# SCH_Voltage-Regulator-AMS1117_2026-08-26.net
KiCad netlist of a schematic drawn in EasyEDA
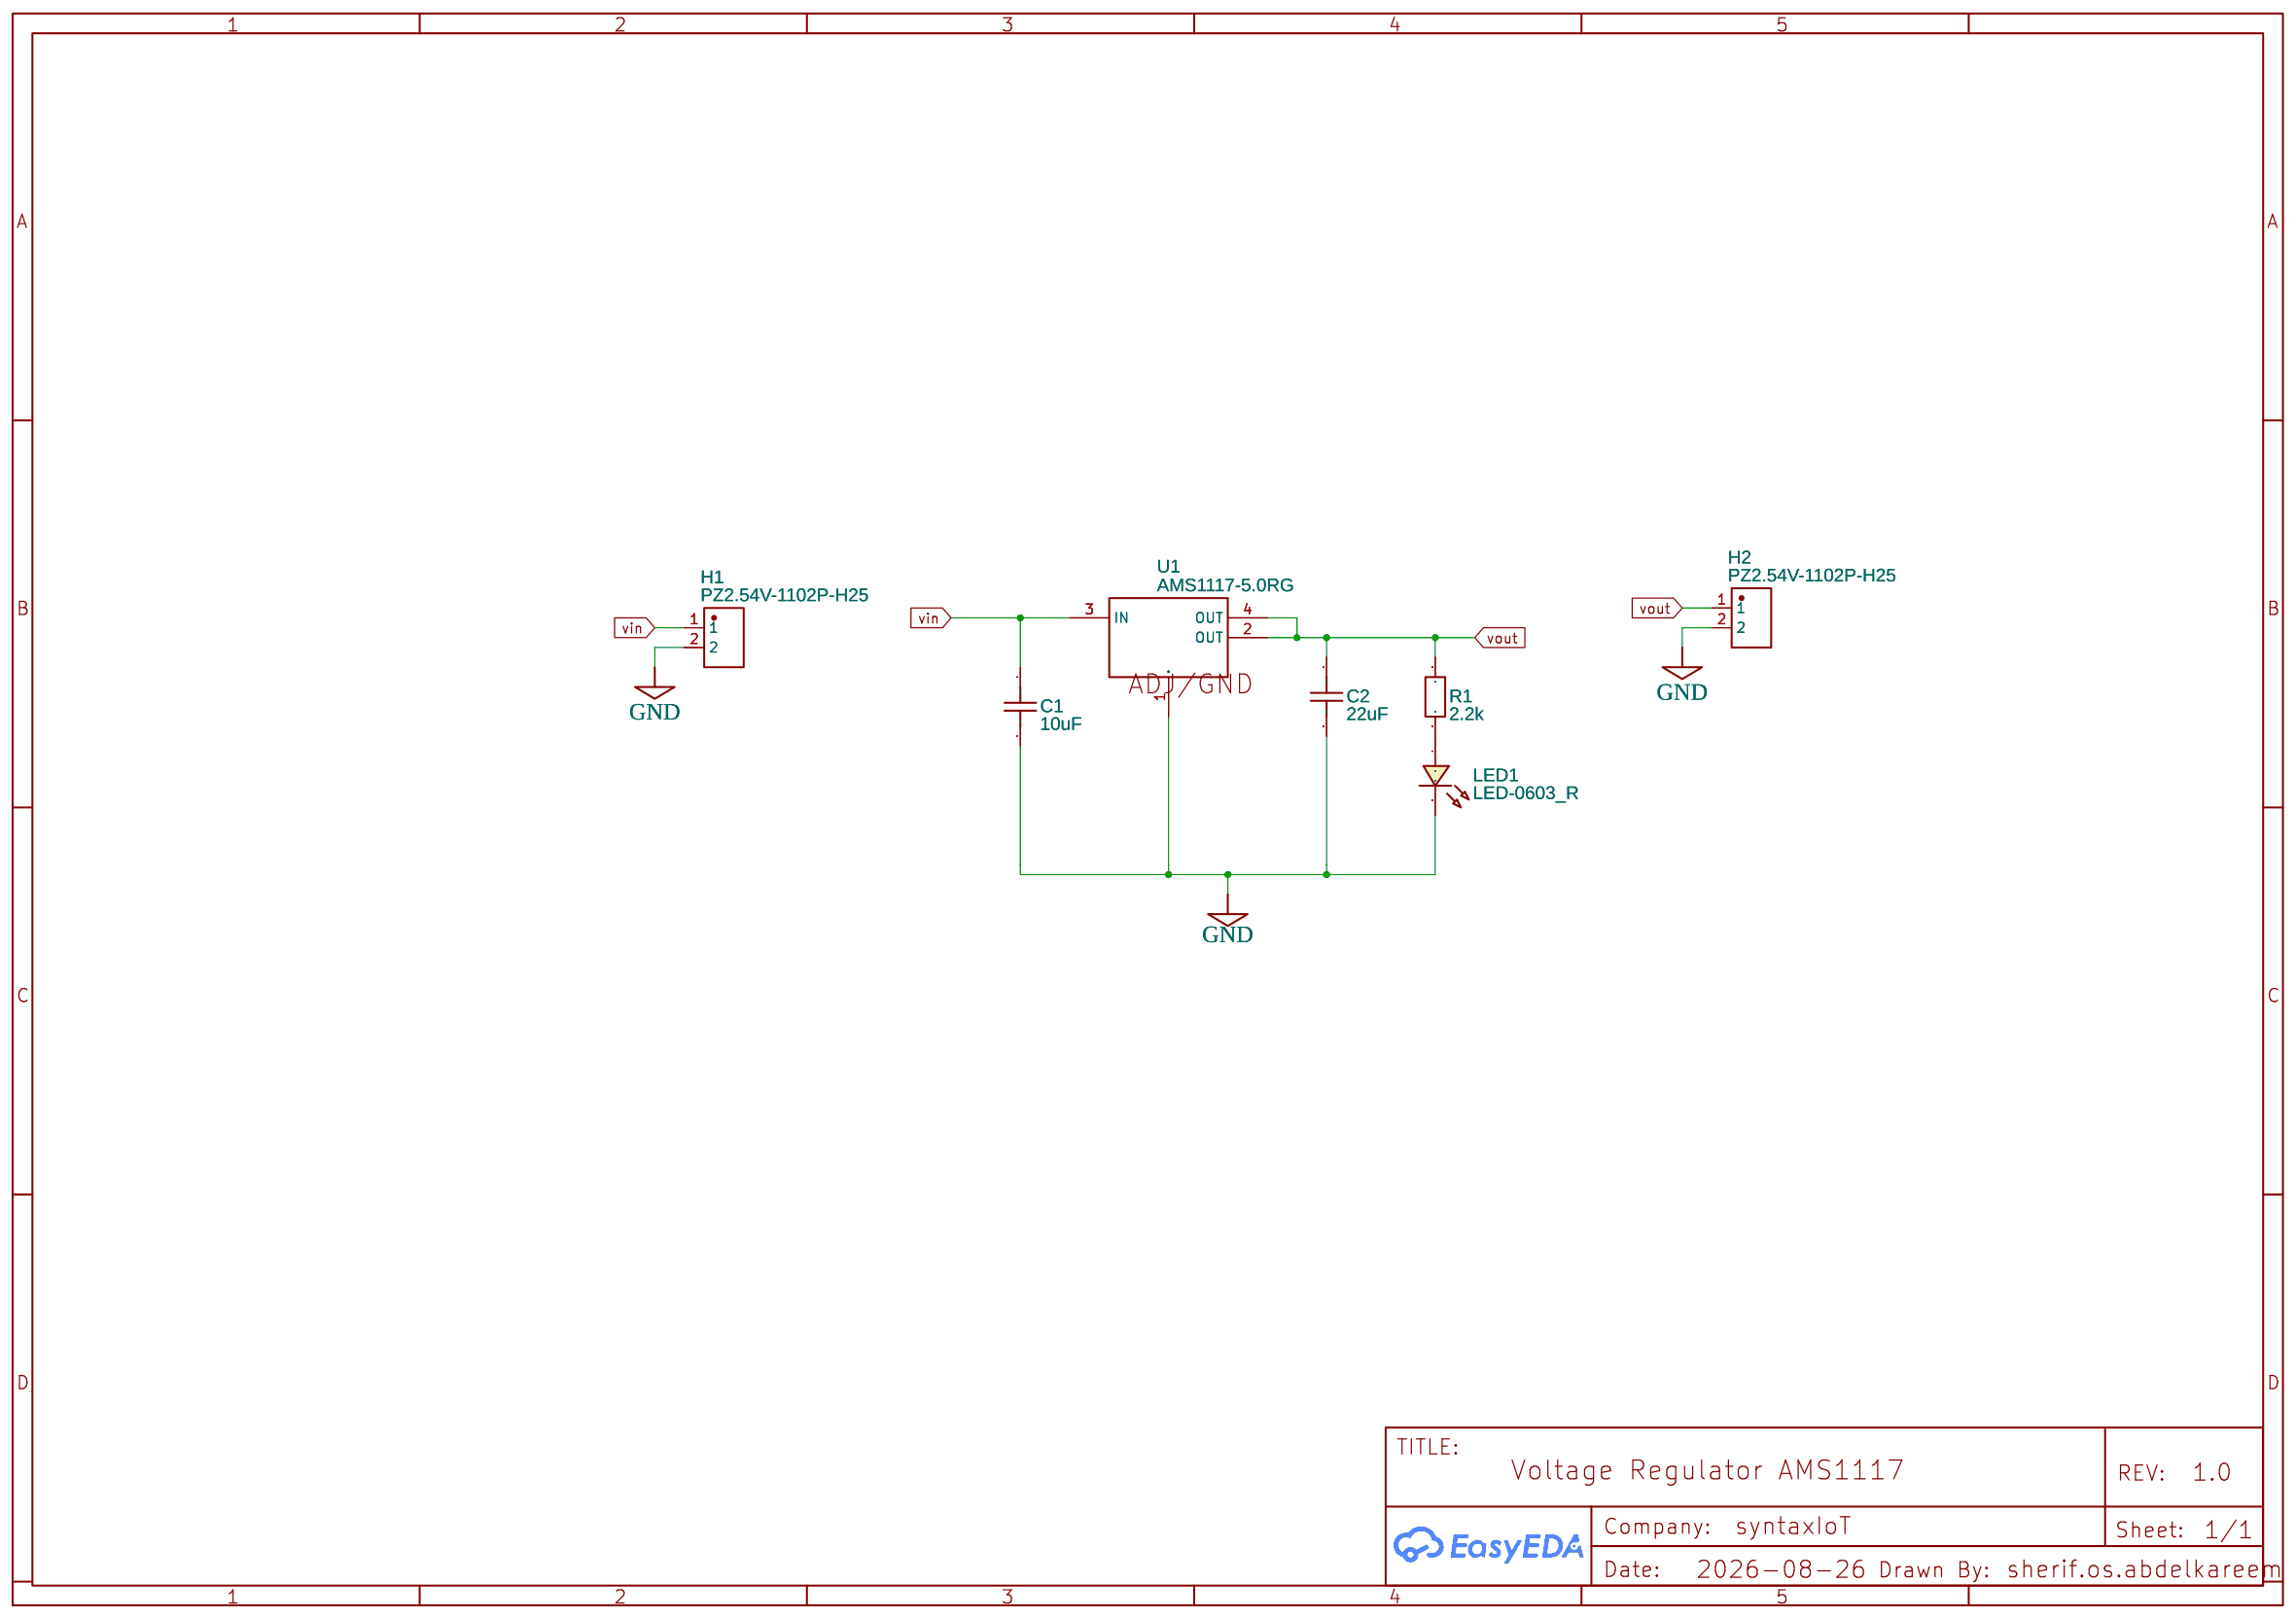
[diagram p0: schematic sheet]

(export (version "E")
  (design (tool "Eeschema 10.0.6"))
  (components
    (comp (ref "C1") (value "10uF") (libsource (lib "") (part "C_0603_US")))
    (comp (ref "C2") (value "22uF") (libsource (lib "") (part "C_0603_US")))
    (comp (ref "H1")
      (value "PZ2.54V-1102P-H25")
      (fields (field (name "Manufacturer") "JXTCONN(聚兴泰)"))
      (libsource (lib "") (part "PZ2.54V-1102P-H25"))
    )
    (comp (ref "H2")
      (value "PZ2.54V-1102P-H25")
      (fields (field (name "Manufacturer") "JXTCONN(聚兴泰)"))
      (libsource (lib "") (part "PZ2.54V-1102P-H25"))
    )
    (comp (ref "LED1")
      (value "LED-0603_R")
      (fields
        (field (name "Manufacturer Part") "19-217/R6C-AL1M2VY/3T")
        (field (name "Manufacturer") "EVERLIGHT(台湾亿光)")
      )
      (libsource (lib "") (part "LED-0603_R"))
    )
    (comp (ref "R1") (value "2.2k") (libsource (lib "") (part "R_0603_EU")))
    (comp (ref "U1")
      (value "AMS1117-5.0RG")
      (fields (field (name "Manufacturer") "HGC(深圳汉芯)"))
      (libsource (lib "") (part "AMS1117-5.0RG"))
    )
  )
  (nets
    (net (code "1") (name "GND") (class "Default")
      (node (ref "C1") (pin "2") (pinfunction "2_2") (pintype "unspecified"))
      (node (ref "C2") (pin "2") (pinfunction "2_2") (pintype "unspecified"))
      (node (ref "H1") (pin "2") (pinfunction "2_2") (pintype "unspecified"))
      (node (ref "H2") (pin "2") (pinfunction "2_2") (pintype "unspecified"))
      (node (ref "LED1") (pin "2") (pinfunction "2_2") (pintype "unspecified"))
      (node (ref "U1") (pin "1") (pinfunction "ADJ/GND_1") (pintype "passive"))
    )
    (net (code "2") (name "Net-(LED1-Pad1)") (class "Default")
      (node (ref "LED1") (pin "1") (pinfunction "1_1") (pintype "unspecified"))
      (node (ref "R1") (pin "1") (pinfunction "1_1") (pintype "unspecified"))
    )
    (net (code "3") (name "vin") (class "Default")
      (node (ref "C1") (pin "1") (pinfunction "1_1") (pintype "unspecified"))
      (node (ref "H1") (pin "1") (pinfunction "1_1") (pintype "unspecified"))
      (node (ref "U1") (pin "3") (pinfunction "IN_3") (pintype "passive"))
    )
    (net (code "4") (name "vout") (class "Default")
      (node (ref "C2") (pin "1") (pinfunction "1_1") (pintype "unspecified"))
      (node (ref "H2") (pin "1") (pinfunction "1_1") (pintype "unspecified"))
      (node (ref "R1") (pin "2") (pinfunction "2_2") (pintype "unspecified"))
      (node (ref "U1") (pin "2") (pinfunction "OUT_2") (pintype "passive"))
      (node (ref "U1") (pin "4") (pinfunction "OUT_4") (pintype "passive"))
    )
  )
)
